# KlusterLab_HMI.net
KiCad netlist of a schematic drawn in Altium Designer
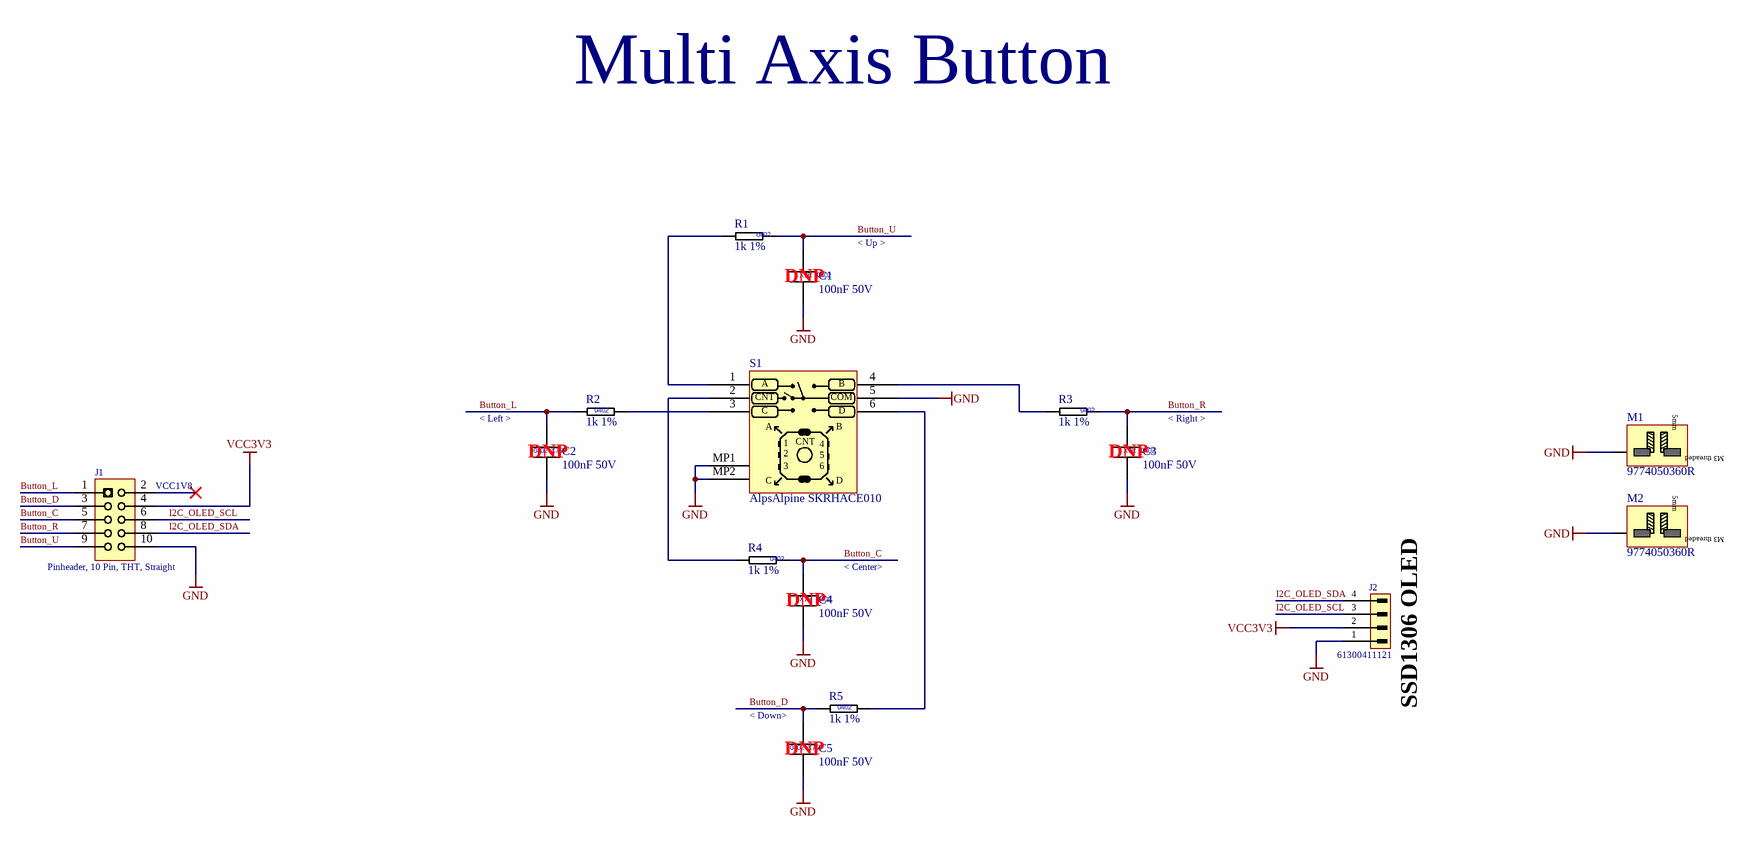
[diagram p0: KlusterLab HMI.SchDoc]

(export (version "E")
  (design (tool "Eeschema 10.0.6"))
  (components
    (comp (ref "C1")
      (value "100nF 50V")
      (footprint "Cap:CAP_0402_L")
      (description "Multilayer Ceramic Capacitors MLCC - SMD/SMT 0402 50VDC")
      (libsource (lib "Cap") (part "CAP_0402_100nF_50V"))
    )
    (comp (ref "C2")
      (value "100nF 50V")
      (footprint "Cap:CAP_0402_L")
      (description "Multilayer Ceramic Capacitors MLCC - SMD/SMT 0402 50VDC")
      (libsource (lib "Cap") (part "CAP_0402_100nF_50V"))
    )
    (comp (ref "C3")
      (value "100nF 50V")
      (footprint "Cap:CAP_0402_L")
      (description "Multilayer Ceramic Capacitors MLCC - SMD/SMT 0402 50VDC")
      (libsource (lib "Cap") (part "CAP_0402_100nF_50V"))
    )
    (comp (ref "C4")
      (value "100nF 50V")
      (footprint "Cap:CAP_0402_L")
      (description "Multilayer Ceramic Capacitors MLCC - SMD/SMT 0402 50VDC")
      (libsource (lib "Cap") (part "CAP_0402_100nF_50V"))
    )
    (comp (ref "C5")
      (value "100nF 50V")
      (footprint "Cap:CAP_0402_L")
      (description "Multilayer Ceramic Capacitors MLCC - SMD/SMT 0402 50VDC")
      (libsource (lib "Cap") (part "CAP_0402_100nF_50V"))
    )
    (comp (ref "J1")
      (value "Pinheader, 10 Pin, THT, Straight")
      (footprint "Conn:62701021621")
      (description "Box Pin header THT 1.27mm 10Pol Straight")
      (libsource (lib "Conn") (part "62701021621_Box Pin header THT 1.27mm 10Pol Straight"))
    )
    (comp (ref "J2")
      (value "WE / WR-PHD / 61300411121 / PinHeader / 1x4 Pin / RM2.54 / Top Entry / Male")
      (footprint "WE_61300411121")
      (description "WR-PHD Pin Header")
      (fields (field (name "SYMBOL TEXT") "61300411121"))
      (libsource (lib "PCB ARTS GMBH") (part "PinHeader_1x4"))
    )
    (comp (ref "M1")
      (value "9774050360R")
      (footprint "Electro_Mech:9774050360R")
      (description "Würth Standoff M3 h:5mm 9774050360R")
      (libsource (lib "Electro_Mech") (part "Würth Standoff M3 h{colon}5mm"))
    )
    (comp (ref "M2")
      (value "9774050360R")
      (footprint "Electro_Mech:9774050360R")
      (description "Würth Standoff M3 h:5mm 9774050360R")
      (libsource (lib "Electro_Mech") (part "Würth Standoff M3 h{colon}5mm"))
    )
    (comp (ref "R1")
      (value "1k 1%")
      (footprint "Res:RES_0402_L")
      (description "Thick Film Resistors - SMD 1kOhm 1%")
      (libsource (lib "Res") (part "RES_0402_1k_1%"))
    )
    (comp (ref "R2")
      (value "1k 1%")
      (footprint "Res:RES_0402_L")
      (description "Thick Film Resistors - SMD 1kOhm 1%")
      (libsource (lib "Res") (part "RES_0402_1k_1%"))
    )
    (comp (ref "R3")
      (value "1k 1%")
      (footprint "Res:RES_0402_L")
      (description "Thick Film Resistors - SMD 1kOhm 1%")
      (libsource (lib "Res") (part "RES_0402_1k_1%"))
    )
    (comp (ref "R4")
      (value "1k 1%")
      (footprint "Res:RES_0402_L")
      (description "Thick Film Resistors - SMD 1kOhm 1%")
      (libsource (lib "Res") (part "RES_0402_1k_1%"))
    )
    (comp (ref "R5")
      (value "1k 1%")
      (footprint "Res:RES_0402_L")
      (description "Thick Film Resistors - SMD 1kOhm 1%")
      (libsource (lib "Res") (part "RES_0402_1k_1%"))
    )
    (comp (ref "S1")
      (value "AlpsAlpine SKRHACE010")
      (footprint "Electro_Mech:AlpsAlpine_SKRHACE010")
      (description "Multi-Directional Switches, 4-directions, center-push")
      (libsource (lib "Electro_Mech") (part "AlpsAlpine_ SKRHACE010_Multi-Directional-Switches_4-directions_center-push"))
    )
  )
  (nets
    (net (code "1") (name "/Button_C") (class "Default")
      (node (ref "C4") (pin "1") (pinfunction "1_1") (pintype "passive"))
      (node (ref "J1") (pin "5") (pinfunction "5_5") (pintype "passive"))
      (node (ref "R4") (pin "1") (pinfunction "1_1") (pintype "passive"))
    )
    (net (code "2") (name "/Button_D") (class "Default")
      (node (ref "C5") (pin "1") (pinfunction "1_1") (pintype "passive"))
      (node (ref "J1") (pin "3") (pinfunction "3_3") (pintype "passive"))
      (node (ref "R5") (pin "1") (pinfunction "1_1") (pintype "passive"))
    )
    (net (code "3") (name "/Button_L") (class "Default")
      (node (ref "C2") (pin "1") (pinfunction "1_1") (pintype "passive"))
      (node (ref "J1") (pin "1") (pinfunction "1_1") (pintype "passive"))
      (node (ref "R2") (pin "1") (pinfunction "1_1") (pintype "passive"))
    )
    (net (code "4") (name "/Button_R") (class "Default")
      (node (ref "C3") (pin "1") (pinfunction "1_1") (pintype "passive"))
      (node (ref "J1") (pin "7") (pinfunction "7_7") (pintype "passive"))
      (node (ref "R3") (pin "1") (pinfunction "1_1") (pintype "passive"))
    )
    (net (code "5") (name "/Button_U") (class "Default")
      (node (ref "C1") (pin "1") (pinfunction "1_1") (pintype "passive"))
      (node (ref "J1") (pin "9") (pinfunction "9_9") (pintype "passive"))
      (node (ref "R1") (pin "1") (pinfunction "1_1") (pintype "passive"))
    )
    (net (code "6") (name "/I2C_OLED_SCL") (class "Default")
      (node (ref "J1") (pin "6") (pinfunction "6_6") (pintype "passive"))
      (node (ref "J2") (pin "3") (pinfunction "3_3") (pintype "passive"))
    )
    (net (code "7") (name "/I2C_OLED_SDA") (class "Default")
      (node (ref "J1") (pin "8") (pinfunction "8_8") (pintype "passive"))
      (node (ref "J2") (pin "4") (pinfunction "4_4") (pintype "passive"))
    )
    (net (code "8") (name "GND") (class "Default")
      (node (ref "C1") (pin "2") (pinfunction "2_2") (pintype "passive"))
      (node (ref "C2") (pin "2") (pinfunction "2_2") (pintype "passive"))
      (node (ref "C3") (pin "2") (pinfunction "2_2") (pintype "passive"))
      (node (ref "C4") (pin "2") (pinfunction "2_2") (pintype "passive"))
      (node (ref "C5") (pin "2") (pinfunction "2_2") (pintype "passive"))
      (node (ref "J1") (pin "10") (pinfunction "10_10") (pintype "passive"))
      (node (ref "J2") (pin "1") (pinfunction "1_1") (pintype "passive"))
      (node (ref "M1") (pin "1") (pinfunction "1_1") (pintype "passive"))
      (node (ref "M2") (pin "1") (pinfunction "1_1") (pintype "passive"))
      (node (ref "S1") (pin "5") (pinfunction "5_5") (pintype "passive"))
      (node (ref "S1") (pin "MP1") (pinfunction "MP1_MP1") (pintype "passive"))
      (node (ref "S1") (pin "MP2") (pinfunction "MP2_MP2") (pintype "passive"))
    )
    (net (code "9") (name "Net-(R1-Pad2)") (class "Default")
      (node (ref "R1") (pin "2") (pinfunction "2_2") (pintype "passive"))
      (node (ref "S1") (pin "1") (pinfunction "1_1") (pintype "passive"))
    )
    (net (code "10") (name "Net-(R2-Pad2)") (class "Default")
      (node (ref "R2") (pin "2") (pinfunction "2_2") (pintype "passive"))
      (node (ref "S1") (pin "3") (pinfunction "3_3") (pintype "passive"))
    )
    (net (code "11") (name "Net-(R3-Pad2)") (class "Default")
      (node (ref "R3") (pin "2") (pinfunction "2_2") (pintype "passive"))
      (node (ref "S1") (pin "4") (pinfunction "4_4") (pintype "passive"))
    )
    (net (code "12") (name "Net-(R4-Pad2)") (class "Default")
      (node (ref "R4") (pin "2") (pinfunction "2_2") (pintype "passive"))
      (node (ref "S1") (pin "2") (pinfunction "2_2") (pintype "passive"))
    )
    (net (code "13") (name "Net-(R5-Pad2)") (class "Default")
      (node (ref "R5") (pin "2") (pinfunction "2_2") (pintype "passive"))
      (node (ref "S1") (pin "6") (pinfunction "6_6") (pintype "passive"))
    )
    (net (code "14") (name "VCC3V3") (class "Default")
      (node (ref "J1") (pin "4") (pinfunction "4_4") (pintype "passive"))
      (node (ref "J2") (pin "2") (pinfunction "2_2") (pintype "passive"))
    )
    (net (code "15") (name "unconnected-(J1-Pad2)") (class "Default")
      (node (ref "J1") (pin "2") (pinfunction "2_2") (pintype "passive+no_connect"))
    )
  )
)
